# 8266WROOM.net
KiCad netlist of a schematic drawn in Altium Designer
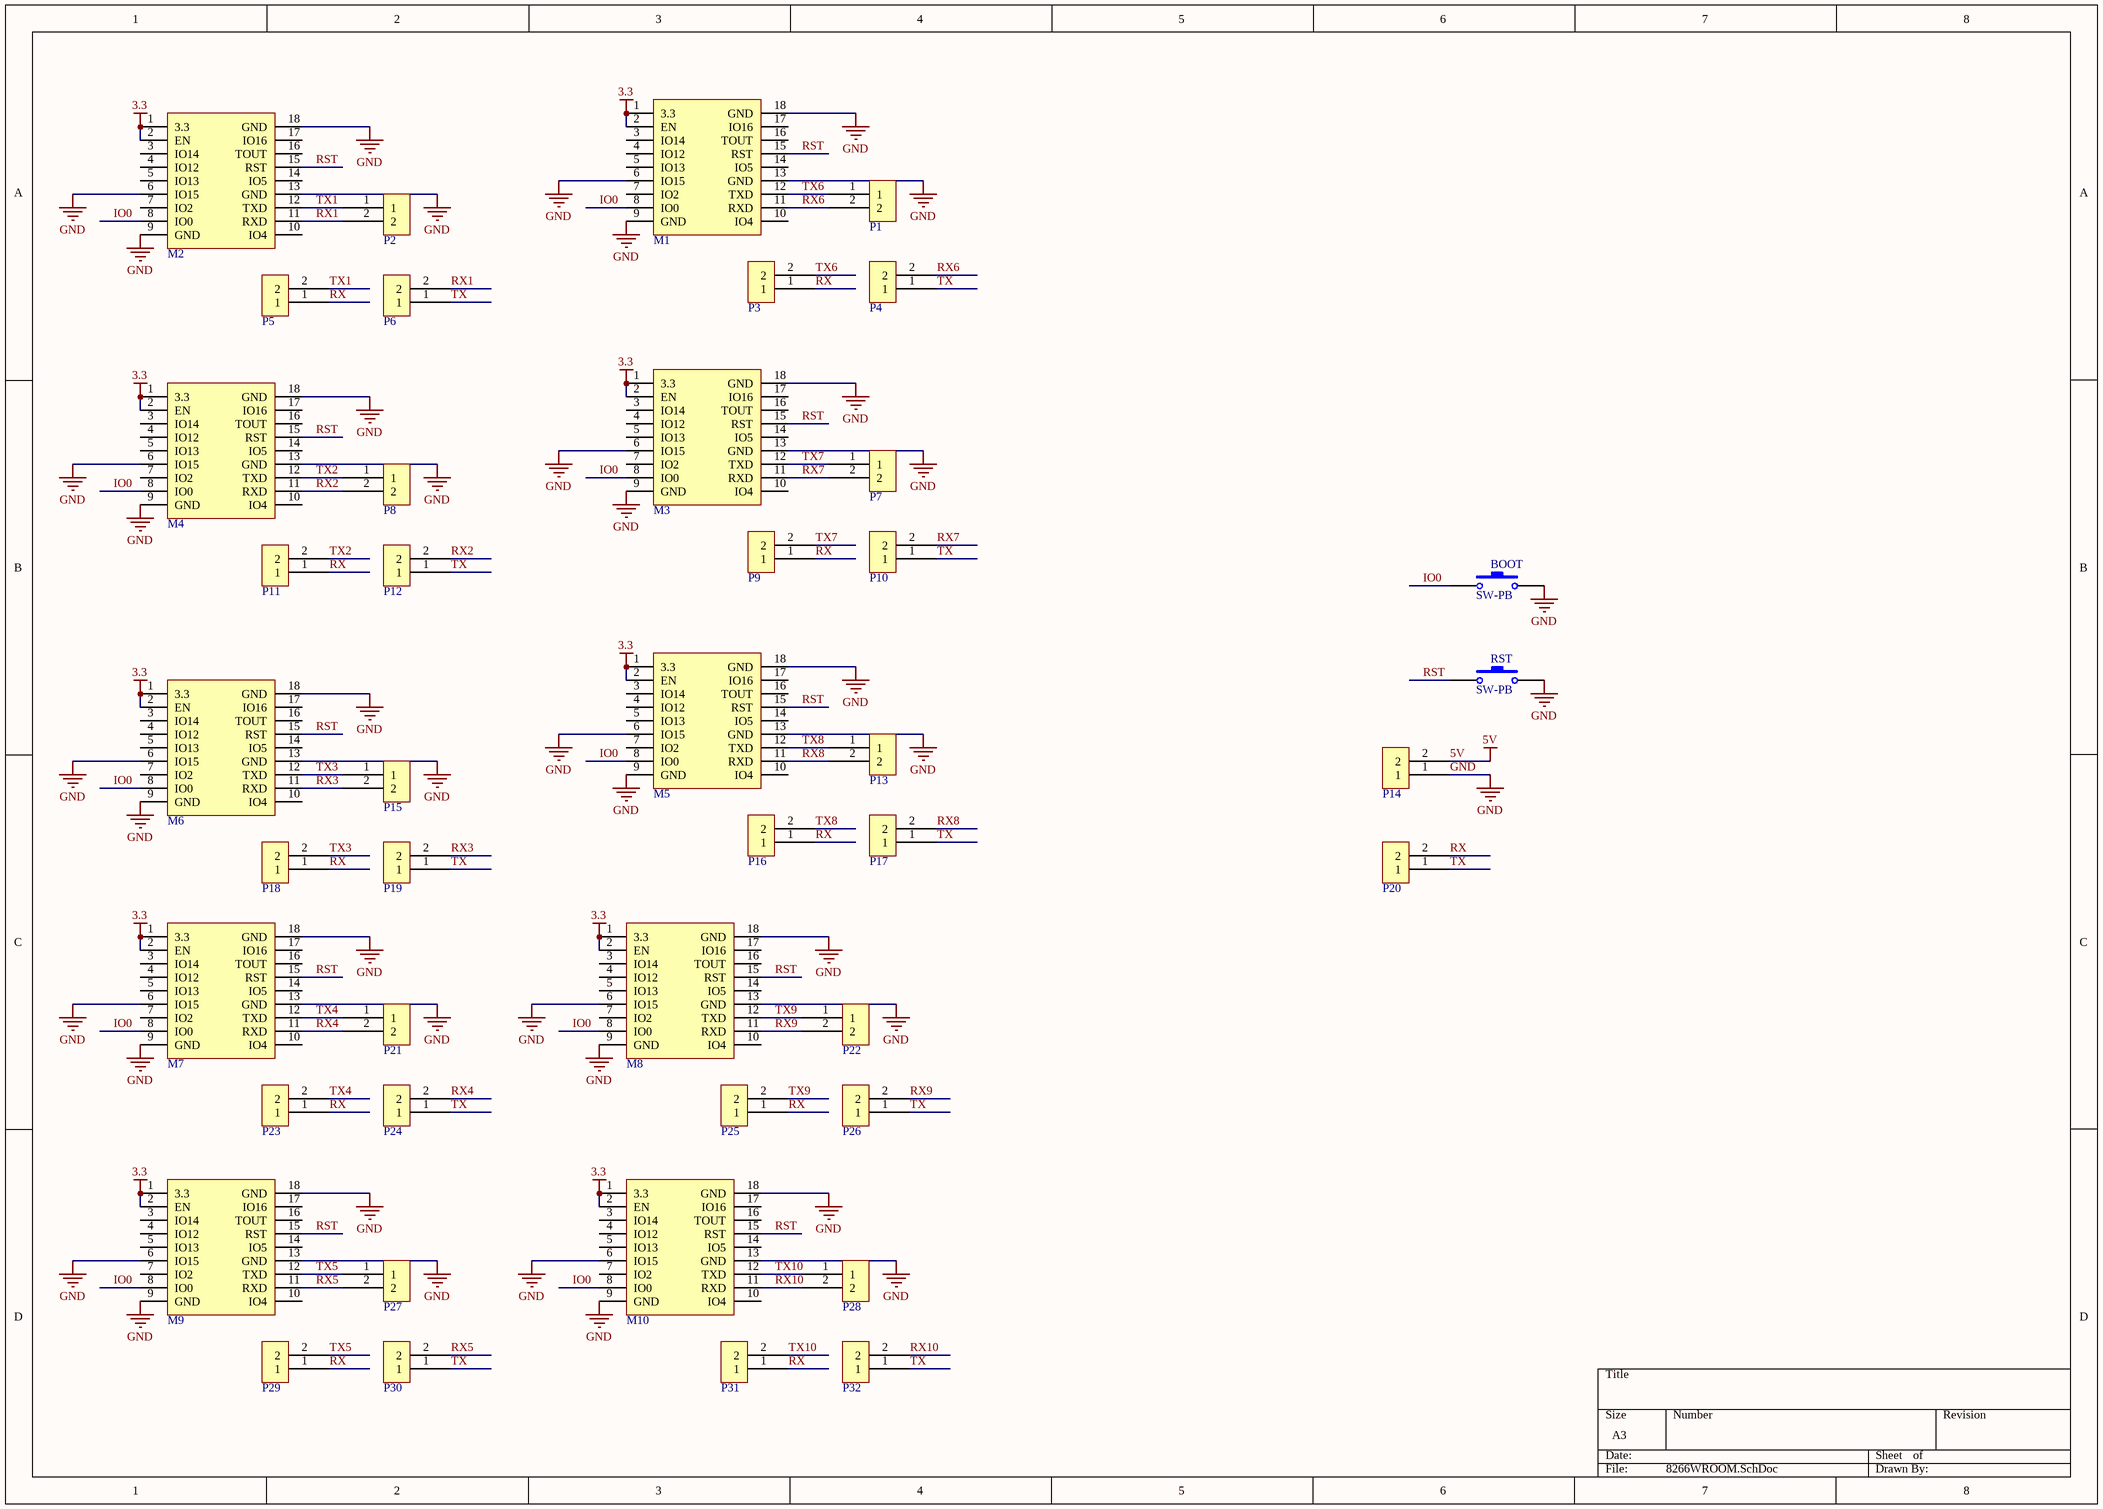
[diagram p0: 8266WROOM.SchDoc]

(export (version "E")
  (design (tool "Eeschema 10.0.6"))
  (components
    (comp (ref "BOOT")
      (value "SW-PB")
      (footprint "SW3x4")
      (description "Switch")
      (fields (field (name "PUBLISHER") "Altium Limited"))
      (libsource (lib "Miscellaneous Devices") (part "SW-PB"))
    )
    (comp (ref "M1")
      (value "ESP8266_WROOM02")
      (footprint "ESP8266-WROOM-02")
      (libsource (lib "WifiGain") (part "ESP8266_WROOM02"))
    )
    (comp (ref "M2")
      (value "ESP8266_WROOM02")
      (footprint "ESP8266-WROOM-02")
      (libsource (lib "WifiGain") (part "ESP8266_WROOM02"))
    )
    (comp (ref "M3")
      (value "ESP8266_WROOM02")
      (footprint "ESP8266-WROOM-02")
      (libsource (lib "WifiGain") (part "ESP8266_WROOM02"))
    )
    (comp (ref "M4")
      (value "ESP8266_WROOM02")
      (footprint "ESP8266-WROOM-02")
      (libsource (lib "WifiGain") (part "ESP8266_WROOM02"))
    )
    (comp (ref "M5")
      (value "ESP8266_WROOM02")
      (footprint "ESP8266-WROOM-02")
      (libsource (lib "WifiGain") (part "ESP8266_WROOM02"))
    )
    (comp (ref "M6")
      (value "ESP8266_WROOM02")
      (footprint "ESP8266-WROOM-02")
      (libsource (lib "WifiGain") (part "ESP8266_WROOM02"))
    )
    (comp (ref "M7")
      (value "ESP8266_WROOM02")
      (footprint "ESP8266-WROOM-02")
      (libsource (lib "WifiGain") (part "ESP8266_WROOM02"))
    )
    (comp (ref "M8")
      (value "ESP8266_WROOM02")
      (footprint "ESP8266-WROOM-02")
      (libsource (lib "WifiGain") (part "ESP8266_WROOM02"))
    )
    (comp (ref "M9")
      (value "ESP8266_WROOM02")
      (footprint "ESP8266-WROOM-02")
      (libsource (lib "WifiGain") (part "ESP8266_WROOM02"))
    )
    (comp (ref "M10")
      (value "ESP8266_WROOM02")
      (footprint "ESP8266-WROOM-02")
      (libsource (lib "WifiGain") (part "ESP8266_WROOM02"))
    )
    (comp (ref "P1") (value "2P") (footprint "2P") (libsource (lib "") (part "2P_1")))
    (comp (ref "P2") (value "2P") (footprint "2P") (libsource (lib "") (part "2P_1")))
    (comp (ref "P3") (value "2P") (footprint "2P") (libsource (lib "sch") (part "2P")))
    (comp (ref "P4") (value "2P") (footprint "2P") (libsource (lib "sch") (part "2P")))
    (comp (ref "P5") (value "2P") (footprint "2P") (libsource (lib "sch") (part "2P")))
    (comp (ref "P6") (value "2P") (footprint "2P") (libsource (lib "sch") (part "2P")))
    (comp (ref "P7") (value "2P") (footprint "2P") (libsource (lib "") (part "2P_1")))
    (comp (ref "P8") (value "2P") (footprint "2P") (libsource (lib "") (part "2P_1")))
    (comp (ref "P9") (value "2P") (footprint "2P") (libsource (lib "sch") (part "2P")))
    (comp (ref "P10") (value "2P") (footprint "2P") (libsource (lib "sch") (part "2P")))
    (comp (ref "P11") (value "2P") (footprint "2P") (libsource (lib "sch") (part "2P")))
    (comp (ref "P12") (value "2P") (footprint "2P") (libsource (lib "sch") (part "2P")))
    (comp (ref "P13") (value "2P") (footprint "2P") (libsource (lib "") (part "2P_1")))
    (comp (ref "P14") (value "2P") (footprint "2P") (libsource (lib "sch") (part "2P")))
    (comp (ref "P15") (value "2P") (footprint "2P") (libsource (lib "") (part "2P_1")))
    (comp (ref "P16") (value "2P") (footprint "2P") (libsource (lib "sch") (part "2P")))
    (comp (ref "P17") (value "2P") (footprint "2P") (libsource (lib "sch") (part "2P")))
    (comp (ref "P18") (value "2P") (footprint "2P") (libsource (lib "sch") (part "2P")))
    (comp (ref "P19") (value "2P") (footprint "2P") (libsource (lib "sch") (part "2P")))
    (comp (ref "P20") (value "2P") (footprint "2P") (libsource (lib "sch") (part "2P")))
    (comp (ref "P21") (value "2P") (footprint "2P") (libsource (lib "") (part "2P_1")))
    (comp (ref "P22") (value "2P") (footprint "2P") (libsource (lib "") (part "2P_1")))
    (comp (ref "P23") (value "2P") (footprint "2P") (libsource (lib "sch") (part "2P")))
    (comp (ref "P24") (value "2P") (footprint "2P") (libsource (lib "sch") (part "2P")))
    (comp (ref "P25") (value "2P") (footprint "2P") (libsource (lib "sch") (part "2P")))
    (comp (ref "P26") (value "2P") (footprint "2P") (libsource (lib "sch") (part "2P")))
    (comp (ref "P27") (value "2P") (footprint "2P") (libsource (lib "") (part "2P_1")))
    (comp (ref "P28") (value "2P") (footprint "2P") (libsource (lib "") (part "2P_1")))
    (comp (ref "P29") (value "2P") (footprint "2P") (libsource (lib "sch") (part "2P")))
    (comp (ref "P30") (value "2P") (footprint "2P") (libsource (lib "sch") (part "2P")))
    (comp (ref "P31") (value "2P") (footprint "2P") (libsource (lib "sch") (part "2P")))
    (comp (ref "P32") (value "2P") (footprint "2P") (libsource (lib "sch") (part "2P")))
    (comp (ref "RST")
      (value "SW-PB")
      (footprint "SW3x4")
      (description "Switch")
      (fields (field (name "PUBLISHER") "Altium Limited"))
      (libsource (lib "Miscellaneous Devices") (part "SW-PB"))
    )
  )
  (nets
    (net (code "1") (name "/IO0") (class "Default")
      (node (ref "BOOT") (pin "1") (pinfunction "1_1") (pintype "passive"))
      (node (ref "M1") (pin "8") (pinfunction "IO0_8") (pintype "passive"))
      (node (ref "M10") (pin "8") (pinfunction "IO0_8") (pintype "passive"))
      (node (ref "M2") (pin "8") (pinfunction "IO0_8") (pintype "passive"))
      (node (ref "M3") (pin "8") (pinfunction "IO0_8") (pintype "passive"))
      (node (ref "M4") (pin "8") (pinfunction "IO0_8") (pintype "passive"))
      (node (ref "M5") (pin "8") (pinfunction "IO0_8") (pintype "passive"))
      (node (ref "M6") (pin "8") (pinfunction "IO0_8") (pintype "passive"))
      (node (ref "M7") (pin "8") (pinfunction "IO0_8") (pintype "passive"))
      (node (ref "M8") (pin "8") (pinfunction "IO0_8") (pintype "passive"))
      (node (ref "M9") (pin "8") (pinfunction "IO0_8") (pintype "passive"))
    )
    (net (code "2") (name "/RST") (class "Default")
      (node (ref "M1") (pin "15") (pinfunction "RST_15") (pintype "passive"))
      (node (ref "M10") (pin "15") (pinfunction "RST_15") (pintype "passive"))
      (node (ref "M2") (pin "15") (pinfunction "RST_15") (pintype "passive"))
      (node (ref "M3") (pin "15") (pinfunction "RST_15") (pintype "passive"))
      (node (ref "M4") (pin "15") (pinfunction "RST_15") (pintype "passive"))
      (node (ref "M5") (pin "15") (pinfunction "RST_15") (pintype "passive"))
      (node (ref "M6") (pin "15") (pinfunction "RST_15") (pintype "passive"))
      (node (ref "M7") (pin "15") (pinfunction "RST_15") (pintype "passive"))
      (node (ref "M8") (pin "15") (pinfunction "RST_15") (pintype "passive"))
      (node (ref "M9") (pin "15") (pinfunction "RST_15") (pintype "passive"))
      (node (ref "RST") (pin "1") (pinfunction "1_1") (pintype "passive"))
    )
    (net (code "3") (name "/RX") (class "Default")
      (node (ref "P11") (pin "1") (pinfunction "1_1") (pintype "passive"))
      (node (ref "P16") (pin "1") (pinfunction "1_1") (pintype "passive"))
      (node (ref "P18") (pin "1") (pinfunction "1_1") (pintype "passive"))
      (node (ref "P20") (pin "2") (pinfunction "2_2") (pintype "passive"))
      (node (ref "P23") (pin "1") (pinfunction "1_1") (pintype "passive"))
      (node (ref "P25") (pin "1") (pinfunction "1_1") (pintype "passive"))
      (node (ref "P29") (pin "1") (pinfunction "1_1") (pintype "passive"))
      (node (ref "P3") (pin "1") (pinfunction "1_1") (pintype "passive"))
      (node (ref "P31") (pin "1") (pinfunction "1_1") (pintype "passive"))
      (node (ref "P5") (pin "1") (pinfunction "1_1") (pintype "passive"))
      (node (ref "P9") (pin "1") (pinfunction "1_1") (pintype "passive"))
    )
    (net (code "4") (name "/RX1") (class "Default")
      (node (ref "M2") (pin "11") (pinfunction "RXD_11") (pintype "passive"))
      (node (ref "P2") (pin "2") (pinfunction "2_2") (pintype "passive"))
      (node (ref "P6") (pin "2") (pinfunction "2_2") (pintype "passive"))
    )
    (net (code "5") (name "/RX2") (class "Default")
      (node (ref "M4") (pin "11") (pinfunction "RXD_11") (pintype "passive"))
      (node (ref "P12") (pin "2") (pinfunction "2_2") (pintype "passive"))
      (node (ref "P8") (pin "2") (pinfunction "2_2") (pintype "passive"))
    )
    (net (code "6") (name "/RX3") (class "Default")
      (node (ref "M6") (pin "11") (pinfunction "RXD_11") (pintype "passive"))
      (node (ref "P15") (pin "2") (pinfunction "2_2") (pintype "passive"))
      (node (ref "P19") (pin "2") (pinfunction "2_2") (pintype "passive"))
    )
    (net (code "7") (name "/RX4") (class "Default")
      (node (ref "M7") (pin "11") (pinfunction "RXD_11") (pintype "passive"))
      (node (ref "P21") (pin "2") (pinfunction "2_2") (pintype "passive"))
      (node (ref "P24") (pin "2") (pinfunction "2_2") (pintype "passive"))
    )
    (net (code "8") (name "/RX5") (class "Default")
      (node (ref "M9") (pin "11") (pinfunction "RXD_11") (pintype "passive"))
      (node (ref "P27") (pin "2") (pinfunction "2_2") (pintype "passive"))
      (node (ref "P30") (pin "2") (pinfunction "2_2") (pintype "passive"))
    )
    (net (code "9") (name "/RX6") (class "Default")
      (node (ref "M1") (pin "11") (pinfunction "RXD_11") (pintype "passive"))
      (node (ref "P1") (pin "2") (pinfunction "2_2") (pintype "passive"))
      (node (ref "P4") (pin "2") (pinfunction "2_2") (pintype "passive"))
    )
    (net (code "10") (name "/RX7") (class "Default")
      (node (ref "M3") (pin "11") (pinfunction "RXD_11") (pintype "passive"))
      (node (ref "P10") (pin "2") (pinfunction "2_2") (pintype "passive"))
      (node (ref "P7") (pin "2") (pinfunction "2_2") (pintype "passive"))
    )
    (net (code "11") (name "/RX8") (class "Default")
      (node (ref "M5") (pin "11") (pinfunction "RXD_11") (pintype "passive"))
      (node (ref "P13") (pin "2") (pinfunction "2_2") (pintype "passive"))
      (node (ref "P17") (pin "2") (pinfunction "2_2") (pintype "passive"))
    )
    (net (code "12") (name "/RX9") (class "Default")
      (node (ref "M8") (pin "11") (pinfunction "RXD_11") (pintype "passive"))
      (node (ref "P22") (pin "2") (pinfunction "2_2") (pintype "passive"))
      (node (ref "P26") (pin "2") (pinfunction "2_2") (pintype "passive"))
    )
    (net (code "13") (name "/RX10") (class "Default")
      (node (ref "M10") (pin "11") (pinfunction "RXD_11") (pintype "passive"))
      (node (ref "P28") (pin "2") (pinfunction "2_2") (pintype "passive"))
      (node (ref "P32") (pin "2") (pinfunction "2_2") (pintype "passive"))
    )
    (net (code "14") (name "/TX") (class "Default")
      (node (ref "P10") (pin "1") (pinfunction "1_1") (pintype "passive"))
      (node (ref "P12") (pin "1") (pinfunction "1_1") (pintype "passive"))
      (node (ref "P17") (pin "1") (pinfunction "1_1") (pintype "passive"))
      (node (ref "P19") (pin "1") (pinfunction "1_1") (pintype "passive"))
      (node (ref "P20") (pin "1") (pinfunction "1_1") (pintype "passive"))
      (node (ref "P24") (pin "1") (pinfunction "1_1") (pintype "passive"))
      (node (ref "P26") (pin "1") (pinfunction "1_1") (pintype "passive"))
      (node (ref "P30") (pin "1") (pinfunction "1_1") (pintype "passive"))
      (node (ref "P32") (pin "1") (pinfunction "1_1") (pintype "passive"))
      (node (ref "P4") (pin "1") (pinfunction "1_1") (pintype "passive"))
      (node (ref "P6") (pin "1") (pinfunction "1_1") (pintype "passive"))
    )
    (net (code "15") (name "/TX1") (class "Default")
      (node (ref "M2") (pin "12") (pinfunction "TXD_12") (pintype "passive"))
      (node (ref "P2") (pin "1") (pinfunction "1_1") (pintype "passive"))
      (node (ref "P5") (pin "2") (pinfunction "2_2") (pintype "passive"))
    )
    (net (code "16") (name "/TX2") (class "Default")
      (node (ref "M4") (pin "12") (pinfunction "TXD_12") (pintype "passive"))
      (node (ref "P11") (pin "2") (pinfunction "2_2") (pintype "passive"))
      (node (ref "P8") (pin "1") (pinfunction "1_1") (pintype "passive"))
    )
    (net (code "17") (name "/TX3") (class "Default")
      (node (ref "M6") (pin "12") (pinfunction "TXD_12") (pintype "passive"))
      (node (ref "P15") (pin "1") (pinfunction "1_1") (pintype "passive"))
      (node (ref "P18") (pin "2") (pinfunction "2_2") (pintype "passive"))
    )
    (net (code "18") (name "/TX4") (class "Default")
      (node (ref "M7") (pin "12") (pinfunction "TXD_12") (pintype "passive"))
      (node (ref "P21") (pin "1") (pinfunction "1_1") (pintype "passive"))
      (node (ref "P23") (pin "2") (pinfunction "2_2") (pintype "passive"))
    )
    (net (code "19") (name "/TX5") (class "Default")
      (node (ref "M9") (pin "12") (pinfunction "TXD_12") (pintype "passive"))
      (node (ref "P27") (pin "1") (pinfunction "1_1") (pintype "passive"))
      (node (ref "P29") (pin "2") (pinfunction "2_2") (pintype "passive"))
    )
    (net (code "20") (name "/TX6") (class "Default")
      (node (ref "M1") (pin "12") (pinfunction "TXD_12") (pintype "passive"))
      (node (ref "P1") (pin "1") (pinfunction "1_1") (pintype "passive"))
      (node (ref "P3") (pin "2") (pinfunction "2_2") (pintype "passive"))
    )
    (net (code "21") (name "/TX7") (class "Default")
      (node (ref "M3") (pin "12") (pinfunction "TXD_12") (pintype "passive"))
      (node (ref "P7") (pin "1") (pinfunction "1_1") (pintype "passive"))
      (node (ref "P9") (pin "2") (pinfunction "2_2") (pintype "passive"))
    )
    (net (code "22") (name "/TX8") (class "Default")
      (node (ref "M5") (pin "12") (pinfunction "TXD_12") (pintype "passive"))
      (node (ref "P13") (pin "1") (pinfunction "1_1") (pintype "passive"))
      (node (ref "P16") (pin "2") (pinfunction "2_2") (pintype "passive"))
    )
    (net (code "23") (name "/TX9") (class "Default")
      (node (ref "M8") (pin "12") (pinfunction "TXD_12") (pintype "passive"))
      (node (ref "P22") (pin "1") (pinfunction "1_1") (pintype "passive"))
      (node (ref "P25") (pin "2") (pinfunction "2_2") (pintype "passive"))
    )
    (net (code "24") (name "/TX10") (class "Default")
      (node (ref "M10") (pin "12") (pinfunction "TXD_12") (pintype "passive"))
      (node (ref "P28") (pin "1") (pinfunction "1_1") (pintype "passive"))
      (node (ref "P31") (pin "2") (pinfunction "2_2") (pintype "passive"))
    )
    (net (code "25") (name "3.3") (class "Default")
      (node (ref "M1") (pin "1") (pinfunction "3.3_1") (pintype "passive"))
      (node (ref "M1") (pin "2") (pinfunction "EN_2") (pintype "passive"))
      (node (ref "M10") (pin "1") (pinfunction "3.3_1") (pintype "passive"))
      (node (ref "M10") (pin "2") (pinfunction "EN_2") (pintype "passive"))
      (node (ref "M2") (pin "1") (pinfunction "3.3_1") (pintype "passive"))
      (node (ref "M2") (pin "2") (pinfunction "EN_2") (pintype "passive"))
      (node (ref "M3") (pin "1") (pinfunction "3.3_1") (pintype "passive"))
      (node (ref "M3") (pin "2") (pinfunction "EN_2") (pintype "passive"))
      (node (ref "M4") (pin "1") (pinfunction "3.3_1") (pintype "passive"))
      (node (ref "M4") (pin "2") (pinfunction "EN_2") (pintype "passive"))
      (node (ref "M5") (pin "1") (pinfunction "3.3_1") (pintype "passive"))
      (node (ref "M5") (pin "2") (pinfunction "EN_2") (pintype "passive"))
      (node (ref "M6") (pin "1") (pinfunction "3.3_1") (pintype "passive"))
      (node (ref "M6") (pin "2") (pinfunction "EN_2") (pintype "passive"))
      (node (ref "M7") (pin "1") (pinfunction "3.3_1") (pintype "passive"))
      (node (ref "M7") (pin "2") (pinfunction "EN_2") (pintype "passive"))
      (node (ref "M8") (pin "1") (pinfunction "3.3_1") (pintype "passive"))
      (node (ref "M8") (pin "2") (pinfunction "EN_2") (pintype "passive"))
      (node (ref "M9") (pin "1") (pinfunction "3.3_1") (pintype "passive"))
      (node (ref "M9") (pin "2") (pinfunction "EN_2") (pintype "passive"))
    )
    (net (code "26") (name "5V") (class "Default")
      (node (ref "P14") (pin "2") (pinfunction "2_2") (pintype "passive"))
    )
    (net (code "27") (name "GND") (class "Default")
      (node (ref "BOOT") (pin "2") (pinfunction "2_2") (pintype "passive"))
      (node (ref "M1") (pin "13") (pinfunction "GND_13") (pintype "passive"))
      (node (ref "M1") (pin "18") (pinfunction "GND_18") (pintype "passive"))
      (node (ref "M1") (pin "6") (pinfunction "IO15_6") (pintype "passive"))
      (node (ref "M1") (pin "9") (pinfunction "GND_9") (pintype "passive"))
      (node (ref "M10") (pin "13") (pinfunction "GND_13") (pintype "passive"))
      (node (ref "M10") (pin "18") (pinfunction "GND_18") (pintype "passive"))
      (node (ref "M10") (pin "6") (pinfunction "IO15_6") (pintype "passive"))
      (node (ref "M10") (pin "9") (pinfunction "GND_9") (pintype "passive"))
      (node (ref "M2") (pin "13") (pinfunction "GND_13") (pintype "passive"))
      (node (ref "M2") (pin "18") (pinfunction "GND_18") (pintype "passive"))
      (node (ref "M2") (pin "6") (pinfunction "IO15_6") (pintype "passive"))
      (node (ref "M2") (pin "9") (pinfunction "GND_9") (pintype "passive"))
      (node (ref "M3") (pin "13") (pinfunction "GND_13") (pintype "passive"))
      (node (ref "M3") (pin "18") (pinfunction "GND_18") (pintype "passive"))
      (node (ref "M3") (pin "6") (pinfunction "IO15_6") (pintype "passive"))
      (node (ref "M3") (pin "9") (pinfunction "GND_9") (pintype "passive"))
      (node (ref "M4") (pin "13") (pinfunction "GND_13") (pintype "passive"))
      (node (ref "M4") (pin "18") (pinfunction "GND_18") (pintype "passive"))
      (node (ref "M4") (pin "6") (pinfunction "IO15_6") (pintype "passive"))
      (node (ref "M4") (pin "9") (pinfunction "GND_9") (pintype "passive"))
      (node (ref "M5") (pin "13") (pinfunction "GND_13") (pintype "passive"))
      (node (ref "M5") (pin "18") (pinfunction "GND_18") (pintype "passive"))
      (node (ref "M5") (pin "6") (pinfunction "IO15_6") (pintype "passive"))
      (node (ref "M5") (pin "9") (pinfunction "GND_9") (pintype "passive"))
      (node (ref "M6") (pin "13") (pinfunction "GND_13") (pintype "passive"))
      (node (ref "M6") (pin "18") (pinfunction "GND_18") (pintype "passive"))
      (node (ref "M6") (pin "6") (pinfunction "IO15_6") (pintype "passive"))
      (node (ref "M6") (pin "9") (pinfunction "GND_9") (pintype "passive"))
      (node (ref "M7") (pin "13") (pinfunction "GND_13") (pintype "passive"))
      (node (ref "M7") (pin "18") (pinfunction "GND_18") (pintype "passive"))
      (node (ref "M7") (pin "6") (pinfunction "IO15_6") (pintype "passive"))
      (node (ref "M7") (pin "9") (pinfunction "GND_9") (pintype "passive"))
      (node (ref "M8") (pin "13") (pinfunction "GND_13") (pintype "passive"))
      (node (ref "M8") (pin "18") (pinfunction "GND_18") (pintype "passive"))
      (node (ref "M8") (pin "6") (pinfunction "IO15_6") (pintype "passive"))
      (node (ref "M8") (pin "9") (pinfunction "GND_9") (pintype "passive"))
      (node (ref "M9") (pin "13") (pinfunction "GND_13") (pintype "passive"))
      (node (ref "M9") (pin "18") (pinfunction "GND_18") (pintype "passive"))
      (node (ref "M9") (pin "6") (pinfunction "IO15_6") (pintype "passive"))
      (node (ref "M9") (pin "9") (pinfunction "GND_9") (pintype "passive"))
      (node (ref "P14") (pin "1") (pinfunction "1_1") (pintype "passive"))
      (node (ref "RST") (pin "2") (pinfunction "2_2") (pintype "passive"))
    )
    (net (code "28") (name "unconnected-(M1-IO2-Pad7)") (class "Default")
      (node (ref "M1") (pin "7") (pinfunction "IO2_7") (pintype "passive"))
    )
    (net (code "29") (name "unconnected-(M1-IO4-Pad10)") (class "Default")
      (node (ref "M1") (pin "10") (pinfunction "IO4_10") (pintype "passive"))
    )
    (net (code "30") (name "unconnected-(M1-IO5-Pad14)") (class "Default")
      (node (ref "M1") (pin "14") (pinfunction "IO5_14") (pintype "passive"))
    )
    (net (code "31") (name "unconnected-(M1-IO12-Pad4)") (class "Default")
      (node (ref "M1") (pin "4") (pinfunction "IO12_4") (pintype "passive"))
    )
    (net (code "32") (name "unconnected-(M1-IO13-Pad5)") (class "Default")
      (node (ref "M1") (pin "5") (pinfunction "IO13_5") (pintype "passive"))
    )
    (net (code "33") (name "unconnected-(M1-IO14-Pad3)") (class "Default")
      (node (ref "M1") (pin "3") (pinfunction "IO14_3") (pintype "passive"))
    )
    (net (code "34") (name "unconnected-(M1-IO16-Pad17)") (class "Default")
      (node (ref "M1") (pin "17") (pinfunction "IO16_17") (pintype "passive"))
    )
    (net (code "35") (name "unconnected-(M1-TOUT-Pad16)") (class "Default")
      (node (ref "M1") (pin "16") (pinfunction "TOUT_16") (pintype "passive"))
    )
    (net (code "36") (name "unconnected-(M2-IO2-Pad7)") (class "Default")
      (node (ref "M2") (pin "7") (pinfunction "IO2_7") (pintype "passive"))
    )
    (net (code "37") (name "unconnected-(M2-IO4-Pad10)") (class "Default")
      (node (ref "M2") (pin "10") (pinfunction "IO4_10") (pintype "passive"))
    )
    (net (code "38") (name "unconnected-(M2-IO5-Pad14)") (class "Default")
      (node (ref "M2") (pin "14") (pinfunction "IO5_14") (pintype "passive"))
    )
    (net (code "39") (name "unconnected-(M2-IO12-Pad4)") (class "Default")
      (node (ref "M2") (pin "4") (pinfunction "IO12_4") (pintype "passive"))
    )
    (net (code "40") (name "unconnected-(M2-IO13-Pad5)") (class "Default")
      (node (ref "M2") (pin "5") (pinfunction "IO13_5") (pintype "passive"))
    )
    (net (code "41") (name "unconnected-(M2-IO14-Pad3)") (class "Default")
      (node (ref "M2") (pin "3") (pinfunction "IO14_3") (pintype "passive"))
    )
    (net (code "42") (name "unconnected-(M2-IO16-Pad17)") (class "Default")
      (node (ref "M2") (pin "17") (pinfunction "IO16_17") (pintype "passive"))
    )
    (net (code "43") (name "unconnected-(M2-TOUT-Pad16)") (class "Default")
      (node (ref "M2") (pin "16") (pinfunction "TOUT_16") (pintype "passive"))
    )
    (net (code "44") (name "unconnected-(M3-IO2-Pad7)") (class "Default")
      (node (ref "M3") (pin "7") (pinfunction "IO2_7") (pintype "passive"))
    )
    (net (code "45") (name "unconnected-(M3-IO4-Pad10)") (class "Default")
      (node (ref "M3") (pin "10") (pinfunction "IO4_10") (pintype "passive"))
    )
    (net (code "46") (name "unconnected-(M3-IO5-Pad14)") (class "Default")
      (node (ref "M3") (pin "14") (pinfunction "IO5_14") (pintype "passive"))
    )
    (net (code "47") (name "unconnected-(M3-IO12-Pad4)") (class "Default")
      (node (ref "M3") (pin "4") (pinfunction "IO12_4") (pintype "passive"))
    )
    (net (code "48") (name "unconnected-(M3-IO13-Pad5)") (class "Default")
      (node (ref "M3") (pin "5") (pinfunction "IO13_5") (pintype "passive"))
    )
    (net (code "49") (name "unconnected-(M3-IO14-Pad3)") (class "Default")
      (node (ref "M3") (pin "3") (pinfunction "IO14_3") (pintype "passive"))
    )
    (net (code "50") (name "unconnected-(M3-IO16-Pad17)") (class "Default")
      (node (ref "M3") (pin "17") (pinfunction "IO16_17") (pintype "passive"))
    )
    (net (code "51") (name "unconnected-(M3-TOUT-Pad16)") (class "Default")
      (node (ref "M3") (pin "16") (pinfunction "TOUT_16") (pintype "passive"))
    )
    (net (code "52") (name "unconnected-(M4-IO2-Pad7)") (class "Default")
      (node (ref "M4") (pin "7") (pinfunction "IO2_7") (pintype "passive"))
    )
    (net (code "53") (name "unconnected-(M4-IO4-Pad10)") (class "Default")
      (node (ref "M4") (pin "10") (pinfunction "IO4_10") (pintype "passive"))
    )
    (net (code "54") (name "unconnected-(M4-IO5-Pad14)") (class "Default")
      (node (ref "M4") (pin "14") (pinfunction "IO5_14") (pintype "passive"))
    )
    (net (code "55") (name "unconnected-(M4-IO12-Pad4)") (class "Default")
      (node (ref "M4") (pin "4") (pinfunction "IO12_4") (pintype "passive"))
    )
    (net (code "56") (name "unconnected-(M4-IO13-Pad5)") (class "Default")
      (node (ref "M4") (pin "5") (pinfunction "IO13_5") (pintype "passive"))
    )
    (net (code "57") (name "unconnected-(M4-IO14-Pad3)") (class "Default")
      (node (ref "M4") (pin "3") (pinfunction "IO14_3") (pintype "passive"))
    )
    (net (code "58") (name "unconnected-(M4-IO16-Pad17)") (class "Default")
      (node (ref "M4") (pin "17") (pinfunction "IO16_17") (pintype "passive"))
    )
    (net (code "59") (name "unconnected-(M4-TOUT-Pad16)") (class "Default")
      (node (ref "M4") (pin "16") (pinfunction "TOUT_16") (pintype "passive"))
    )
    (net (code "60") (name "unconnected-(M5-IO2-Pad7)") (class "Default")
      (node (ref "M5") (pin "7") (pinfunction "IO2_7") (pintype "passive"))
    )
    (net (code "61") (name "unconnected-(M5-IO4-Pad10)") (class "Default")
      (node (ref "M5") (pin "10") (pinfunction "IO4_10") (pintype "passive"))
    )
    (net (code "62") (name "unconnected-(M5-IO5-Pad14)") (class "Default")
      (node (ref "M5") (pin "14") (pinfunction "IO5_14") (pintype "passive"))
    )
    (net (code "63") (name "unconnected-(M5-IO12-Pad4)") (class "Default")
      (node (ref "M5") (pin "4") (pinfunction "IO12_4") (pintype "passive"))
    )
    (net (code "64") (name "unconnected-(M5-IO13-Pad5)") (class "Default")
      (node (ref "M5") (pin "5") (pinfunction "IO13_5") (pintype "passive"))
    )
    (net (code "65") (name "unconnected-(M5-IO14-Pad3)") (class "Default")
      (node (ref "M5") (pin "3") (pinfunction "IO14_3") (pintype "passive"))
    )
    (net (code "66") (name "unconnected-(M5-IO16-Pad17)") (class "Default")
      (node (ref "M5") (pin "17") (pinfunction "IO16_17") (pintype "passive"))
    )
    (net (code "67") (name "unconnected-(M5-TOUT-Pad16)") (class "Default")
      (node (ref "M5") (pin "16") (pinfunction "TOUT_16") (pintype "passive"))
    )
    (net (code "68") (name "unconnected-(M6-IO2-Pad7)") (class "Default")
      (node (ref "M6") (pin "7") (pinfunction "IO2_7") (pintype "passive"))
    )
    (net (code "69") (name "unconnected-(M6-IO4-Pad10)") (class "Default")
      (node (ref "M6") (pin "10") (pinfunction "IO4_10") (pintype "passive"))
    )
    (net (code "70") (name "unconnected-(M6-IO5-Pad14)") (class "Default")
      (node (ref "M6") (pin "14") (pinfunction "IO5_14") (pintype "passive"))
    )
    (net (code "71") (name "unconnected-(M6-IO12-Pad4)") (class "Default")
      (node (ref "M6") (pin "4") (pinfunction "IO12_4") (pintype "passive"))
    )
    (net (code "72") (name "unconnected-(M6-IO13-Pad5)") (class "Default")
      (node (ref "M6") (pin "5") (pinfunction "IO13_5") (pintype "passive"))
    )
    (net (code "73") (name "unconnected-(M6-IO14-Pad3)") (class "Default")
      (node (ref "M6") (pin "3") (pinfunction "IO14_3") (pintype "passive"))
    )
    (net (code "74") (name "unconnected-(M6-IO16-Pad17)") (class "Default")
      (node (ref "M6") (pin "17") (pinfunction "IO16_17") (pintype "passive"))
    )
    (net (code "75") (name "unconnected-(M6-TOUT-Pad16)") (class "Default")
      (node (ref "M6") (pin "16") (pinfunction "TOUT_16") (pintype "passive"))
    )
    (net (code "76") (name "unconnected-(M7-IO2-Pad7)") (class "Default")
      (node (ref "M7") (pin "7") (pinfunction "IO2_7") (pintype "passive"))
    )
    (net (code "77") (name "unconnected-(M7-IO4-Pad10)") (class "Default")
      (node (ref "M7") (pin "10") (pinfunction "IO4_10") (pintype "passive"))
    )
    (net (code "78") (name "unconnected-(M7-IO5-Pad14)") (class "Default")
      (node (ref "M7") (pin "14") (pinfunction "IO5_14") (pintype "passive"))
    )
    (net (code "79") (name "unconnected-(M7-IO12-Pad4)") (class "Default")
      (node (ref "M7") (pin "4") (pinfunction "IO12_4") (pintype "passive"))
    )
    (net (code "80") (name "unconnected-(M7-IO13-Pad5)") (class "Default")
      (node (ref "M7") (pin "5") (pinfunction "IO13_5") (pintype "passive"))
    )
    (net (code "81") (name "unconnected-(M7-IO14-Pad3)") (class "Default")
      (node (ref "M7") (pin "3") (pinfunction "IO14_3") (pintype "passive"))
    )
    (net (code "82") (name "unconnected-(M7-IO16-Pad17)") (class "Default")
      (node (ref "M7") (pin "17") (pinfunction "IO16_17") (pintype "passive"))
    )
    (net (code "83") (name "unconnected-(M7-TOUT-Pad16)") (class "Default")
      (node (ref "M7") (pin "16") (pinfunction "TOUT_16") (pintype "passive"))
    )
    (net (code "84") (name "unconnected-(M8-IO2-Pad7)") (class "Default")
      (node (ref "M8") (pin "7") (pinfunction "IO2_7") (pintype "passive"))
    )
    (net (code "85") (name "unconnected-(M8-IO4-Pad10)") (class "Default")
      (node (ref "M8") (pin "10") (pinfunction "IO4_10") (pintype "passive"))
    )
    (net (code "86") (name "unconnected-(M8-IO5-Pad14)") (class "Default")
      (node (ref "M8") (pin "14") (pinfunction "IO5_14") (pintype "passive"))
    )
    (net (code "87") (name "unconnected-(M8-IO12-Pad4)") (class "Default")
      (node (ref "M8") (pin "4") (pinfunction "IO12_4") (pintype "passive"))
    )
    (net (code "88") (name "unconnected-(M8-IO13-Pad5)") (class "Default")
      (node (ref "M8") (pin "5") (pinfunction "IO13_5") (pintype "passive"))
    )
    (net (code "89") (name "unconnected-(M8-IO14-Pad3)") (class "Default")
      (node (ref "M8") (pin "3") (pinfunction "IO14_3") (pintype "passive"))
    )
    (net (code "90") (name "unconnected-(M8-IO16-Pad17)") (class "Default")
      (node (ref "M8") (pin "17") (pinfunction "IO16_17") (pintype "passive"))
    )
    (net (code "91") (name "unconnected-(M8-TOUT-Pad16)") (class "Default")
      (node (ref "M8") (pin "16") (pinfunction "TOUT_16") (pintype "passive"))
    )
    (net (code "92") (name "unconnected-(M9-IO2-Pad7)") (class "Default")
      (node (ref "M9") (pin "7") (pinfunction "IO2_7") (pintype "passive"))
    )
    (net (code "93") (name "unconnected-(M9-IO4-Pad10)") (class "Default")
      (node (ref "M9") (pin "10") (pinfunction "IO4_10") (pintype "passive"))
    )
    (net (code "94") (name "unconnected-(M9-IO5-Pad14)") (class "Default")
      (node (ref "M9") (pin "14") (pinfunction "IO5_14") (pintype "passive"))
    )
    (net (code "95") (name "unconnected-(M9-IO12-Pad4)") (class "Default")
      (node (ref "M9") (pin "4") (pinfunction "IO12_4") (pintype "passive"))
    )
    (net (code "96") (name "unconnected-(M9-IO13-Pad5)") (class "Default")
      (node (ref "M9") (pin "5") (pinfunction "IO13_5") (pintype "passive"))
    )
    (net (code "97") (name "unconnected-(M9-IO14-Pad3)") (class "Default")
      (node (ref "M9") (pin "3") (pinfunction "IO14_3") (pintype "passive"))
    )
    (net (code "98") (name "unconnected-(M9-IO16-Pad17)") (class "Default")
      (node (ref "M9") (pin "17") (pinfunction "IO16_17") (pintype "passive"))
    )
    (net (code "99") (name "unconnected-(M9-TOUT-Pad16)") (class "Default")
      (node (ref "M9") (pin "16") (pinfunction "TOUT_16") (pintype "passive"))
    )
    (net (code "100") (name "unconnected-(M10-IO2-Pad7)") (class "Default")
      (node (ref "M10") (pin "7") (pinfunction "IO2_7") (pintype "passive"))
    )
    (net (code "101") (name "unconnected-(M10-IO4-Pad10)") (class "Default")
      (node (ref "M10") (pin "10") (pinfunction "IO4_10") (pintype "passive"))
    )
    (net (code "102") (name "unconnected-(M10-IO5-Pad14)") (class "Default")
      (node (ref "M10") (pin "14") (pinfunction "IO5_14") (pintype "passive"))
    )
    (net (code "103") (name "unconnected-(M10-IO12-Pad4)") (class "Default")
      (node (ref "M10") (pin "4") (pinfunction "IO12_4") (pintype "passive"))
    )
    (net (code "104") (name "unconnected-(M10-IO13-Pad5)") (class "Default")
      (node (ref "M10") (pin "5") (pinfunction "IO13_5") (pintype "passive"))
    )
    (net (code "105") (name "unconnected-(M10-IO14-Pad3)") (class "Default")
      (node (ref "M10") (pin "3") (pinfunction "IO14_3") (pintype "passive"))
    )
    (net (code "106") (name "unconnected-(M10-IO16-Pad17)") (class "Default")
      (node (ref "M10") (pin "17") (pinfunction "IO16_17") (pintype "passive"))
    )
    (net (code "107") (name "unconnected-(M10-TOUT-Pad16)") (class "Default")
      (node (ref "M10") (pin "16") (pinfunction "TOUT_16") (pintype "passive"))
    )
  )
)
